# XLAT_AND_JTAG.net
KiCad netlist of a schematic drawn in Altium Designer
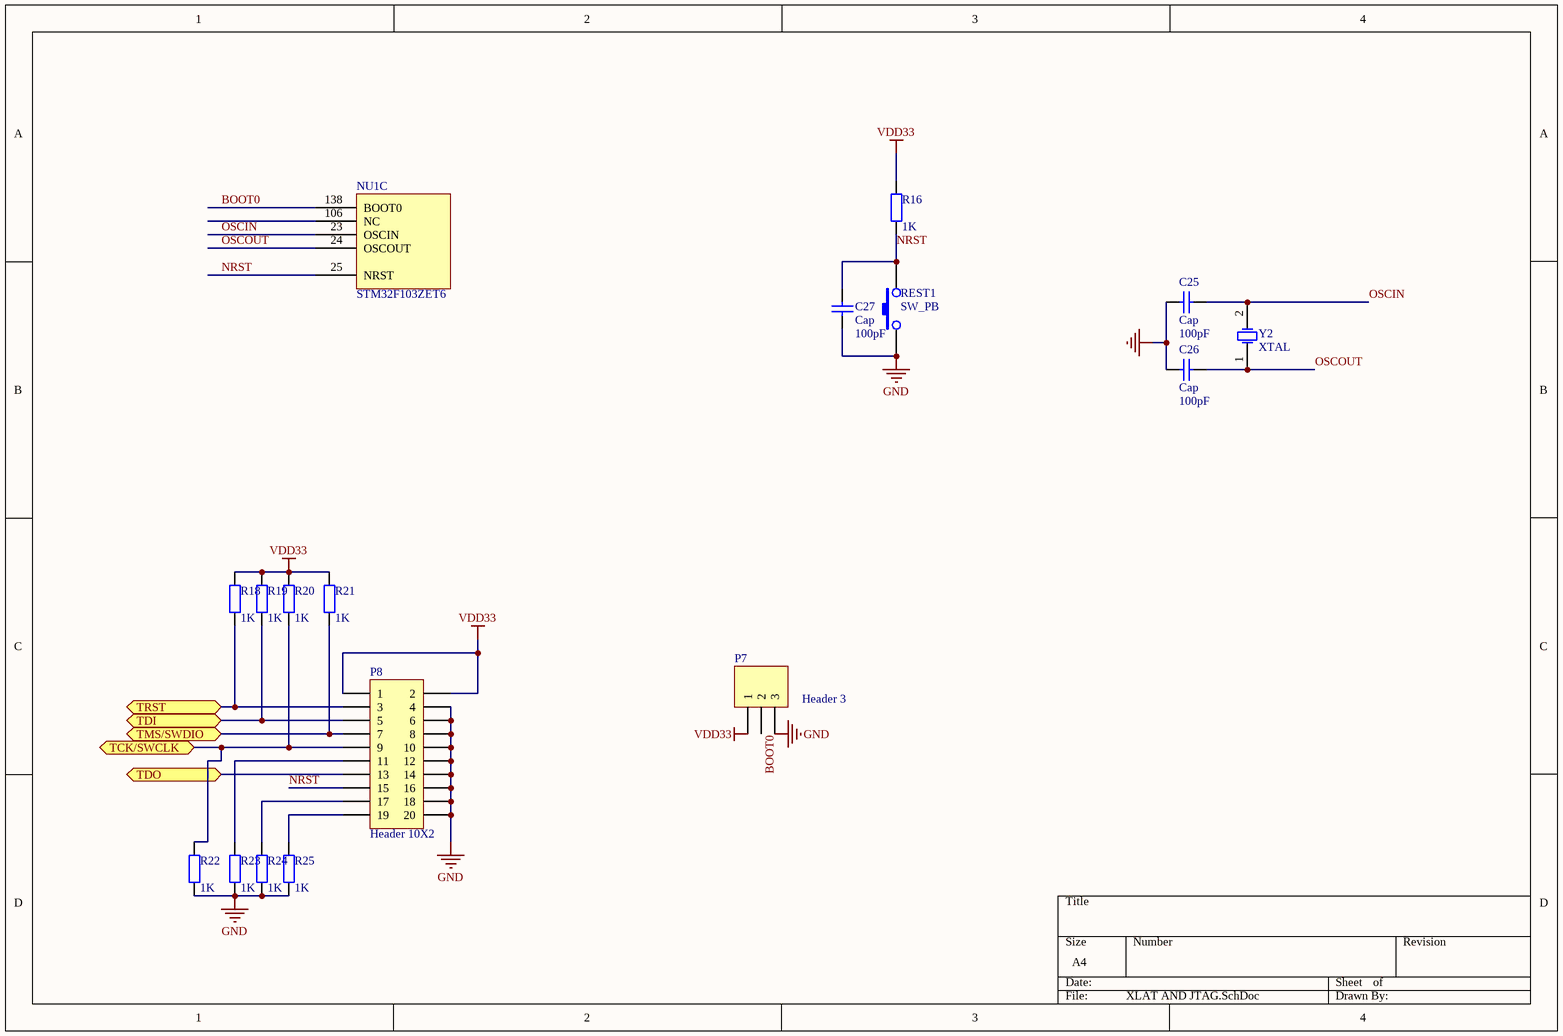
[diagram p0: XLAT AND JTAG.SchDoc]

(export (version "E")
  (design (tool "Eeschema 10.0.6"))
  (components
    (comp (ref "C25")
      (value "Cap")
      (footprint "0805")
      (description "Capacitor")
      (fields (field (name "ALTIUM_VALUE") "100pF") (field (name "PUBLISHER") "Altium Limited"))
      (libsource (lib "Miscellaneous Devices") (part "Cap"))
    )
    (comp (ref "C26")
      (value "Cap")
      (footprint "0805")
      (description "Capacitor")
      (fields (field (name "ALTIUM_VALUE") "100pF") (field (name "PUBLISHER") "Altium Limited"))
      (libsource (lib "Miscellaneous Devices") (part "Cap"))
    )
    (comp (ref "C27")
      (value "Cap")
      (footprint "0805")
      (description "Capacitor")
      (fields (field (name "ALTIUM_VALUE") "100pF") (field (name "PUBLISHER") "Altium Limited"))
      (libsource (lib "Miscellaneous Devices") (part "Cap"))
    )
    (comp (ref "NU1")
      (value "STM32F103ZET6")
      (footprint "LQFN144")
      (libsource (lib "Schlib1") (part "STM32F103ZET6"))
    )
    (comp (ref "P7")
      (value "Header 3")
      (footprint "HDR1X3")
      (description "Header, 3-Pin")
      (fields (field (name "PUBLISHER") "Altium Limited"))
      (libsource (lib "Miscellaneous Connectors") (part "Header 3"))
    )
    (comp (ref "P8")
      (value "Header 10X2")
      (footprint "HDR2X10")
      (description "Header, 10-Pin, Dual row")
      (fields (field (name "PUBLISHER") "Altium Limited"))
      (libsource (lib "Miscellaneous Connectors") (part "Header 10X2"))
    )
    (comp (ref "R16")
      (value "1K")
      (footprint "0805")
      (description "Resistor")
      (fields (field (name "Comment") "Res2") (field (name "PUBLISHER") "Altium Limited"))
      (libsource (lib "Miscellaneous Devices") (part "Res2"))
    )
    (comp (ref "R18")
      (value "1K")
      (footprint "0805")
      (description "Resistor")
      (fields (field (name "Comment") "Res2") (field (name "PUBLISHER") "Altium Limited"))
      (libsource (lib "Miscellaneous Devices") (part "Res2"))
    )
    (comp (ref "R19")
      (value "1K")
      (footprint "0805")
      (description "Resistor")
      (fields (field (name "Comment") "Res2") (field (name "PUBLISHER") "Altium Limited"))
      (libsource (lib "Miscellaneous Devices") (part "Res2"))
    )
    (comp (ref "R20")
      (value "1K")
      (footprint "0805")
      (description "Resistor")
      (fields (field (name "Comment") "Res2") (field (name "PUBLISHER") "Altium Limited"))
      (libsource (lib "Miscellaneous Devices") (part "Res2"))
    )
    (comp (ref "R21")
      (value "1K")
      (footprint "0805")
      (description "Resistor")
      (fields (field (name "Comment") "Res2") (field (name "PUBLISHER") "Altium Limited"))
      (libsource (lib "Miscellaneous Devices") (part "Res2"))
    )
    (comp (ref "R22")
      (value "1K")
      (footprint "0805")
      (description "Resistor")
      (fields (field (name "Comment") "Res2") (field (name "PUBLISHER") "Altium Limited"))
      (libsource (lib "") (part "Res2_1"))
    )
    (comp (ref "R23")
      (value "1K")
      (footprint "0805")
      (description "Resistor")
      (fields (field (name "Comment") "Res2") (field (name "PUBLISHER") "Altium Limited"))
      (libsource (lib "") (part "Res2_1"))
    )
    (comp (ref "R24")
      (value "1K")
      (footprint "0805")
      (description "Resistor")
      (fields (field (name "Comment") "Res2") (field (name "PUBLISHER") "Altium Limited"))
      (libsource (lib "") (part "Res2_1"))
    )
    (comp (ref "R25")
      (value "1K")
      (footprint "0805")
      (description "Resistor")
      (fields (field (name "Comment") "Res2") (field (name "PUBLISHER") "Altium Limited"))
      (libsource (lib "") (part "Res2_1"))
    )
    (comp (ref "REST1") (value "SW_PB") (footprint "SWPB") (libsource (lib "*") (part "SW_PB")))
    (comp (ref "Y2")
      (value "XTAL")
      (footprint "XTAL-1")
      (description "Crystal Oscillator")
      (fields (field (name "PUBLISHER") "Altium Limited"))
      (libsource (lib "Miscellaneous Devices") (part "XTAL"))
    )
  )
  (nets
    (net (code "1") (name "/BOOT0") (class "Default")
      (node (ref "NU1") (pin "138") (pinfunction "BOOT0_138") (pintype "passive"))
      (node (ref "P7") (pin "2") (pinfunction "2_2") (pintype "passive"))
    )
    (net (code "2") (name "/NRST") (class "Default")
      (node (ref "C27") (pin "2") (pinfunction "2_2") (pintype "passive"))
      (node (ref "NU1") (pin "25") (pinfunction "NRST_25") (pintype "passive"))
      (node (ref "P8") (pin "15") (pinfunction "15_15") (pintype "passive"))
      (node (ref "R16") (pin "1") (pinfunction "1_1") (pintype "passive"))
      (node (ref "REST1") (pin "2") (pinfunction "2_2") (pintype "passive"))
    )
    (net (code "3") (name "/OSCIN") (class "Default")
      (node (ref "C25") (pin "2") (pinfunction "2_2") (pintype "passive"))
      (node (ref "NU1") (pin "23") (pinfunction "OSCIN_23") (pintype "passive"))
      (node (ref "Y2") (pin "2") (pinfunction "OSC2_2") (pintype "passive"))
    )
    (net (code "4") (name "/OSCOUT") (class "Default")
      (node (ref "C26") (pin "2") (pinfunction "2_2") (pintype "passive"))
      (node (ref "NU1") (pin "24") (pinfunction "OSCOUT_24") (pintype "passive"))
      (node (ref "Y2") (pin "1") (pinfunction "OSC1_1") (pintype "passive"))
    )
    (net (code "5") (name "/TCK{slash}SWCLK") (class "Default")
      (node (ref "P8") (pin "9") (pinfunction "9_9") (pintype "passive"))
      (node (ref "R20") (pin "1") (pinfunction "1_1") (pintype "passive"))
      (node (ref "R22") (pin "1") (pinfunction "1_1") (pintype "passive"))
    )
    (net (code "6") (name "/TDI") (class "Default")
      (node (ref "P8") (pin "5") (pinfunction "5_5") (pintype "passive"))
      (node (ref "R19") (pin "1") (pinfunction "1_1") (pintype "passive"))
    )
    (net (code "7") (name "/TDO") (class "Default")
      (node (ref "P8") (pin "13") (pinfunction "13_13") (pintype "passive"))
    )
    (net (code "8") (name "/TMS{slash}SWDIO") (class "Default")
      (node (ref "P8") (pin "7") (pinfunction "7_7") (pintype "passive"))
      (node (ref "R21") (pin "1") (pinfunction "1_1") (pintype "passive"))
    )
    (net (code "9") (name "/TRST") (class "Default")
      (node (ref "P8") (pin "3") (pinfunction "3_3") (pintype "passive"))
      (node (ref "R18") (pin "1") (pinfunction "1_1") (pintype "passive"))
    )
    (net (code "10") (name "GND") (class "Default")
      (node (ref "C25") (pin "1") (pinfunction "1_1") (pintype "passive"))
      (node (ref "C26") (pin "1") (pinfunction "1_1") (pintype "passive"))
      (node (ref "C27") (pin "1") (pinfunction "1_1") (pintype "passive"))
      (node (ref "P7") (pin "3") (pinfunction "3_3") (pintype "passive"))
      (node (ref "P8") (pin "10") (pinfunction "10_10") (pintype "passive"))
      (node (ref "P8") (pin "12") (pinfunction "12_12") (pintype "passive"))
      (node (ref "P8") (pin "14") (pinfunction "14_14") (pintype "passive"))
      (node (ref "P8") (pin "16") (pinfunction "16_16") (pintype "passive"))
      (node (ref "P8") (pin "18") (pinfunction "18_18") (pintype "passive"))
      (node (ref "P8") (pin "20") (pinfunction "20_20") (pintype "passive"))
      (node (ref "P8") (pin "4") (pinfunction "4_4") (pintype "passive"))
      (node (ref "P8") (pin "6") (pinfunction "6_6") (pintype "passive"))
      (node (ref "P8") (pin "8") (pinfunction "8_8") (pintype "passive"))
      (node (ref "R22") (pin "2") (pinfunction "2_2") (pintype "passive"))
      (node (ref "R23") (pin "2") (pinfunction "2_2") (pintype "passive"))
      (node (ref "R24") (pin "2") (pinfunction "2_2") (pintype "passive"))
      (node (ref "R25") (pin "2") (pinfunction "2_2") (pintype "passive"))
      (node (ref "REST1") (pin "1") (pinfunction "1_1") (pintype "passive"))
    )
    (net (code "11") (name "Net-(P8-Pad11)") (class "Default")
      (node (ref "P8") (pin "11") (pinfunction "11_11") (pintype "passive"))
      (node (ref "R23") (pin "1") (pinfunction "1_1") (pintype "passive"))
    )
    (net (code "12") (name "Net-(P8-Pad17)") (class "Default")
      (node (ref "P8") (pin "17") (pinfunction "17_17") (pintype "passive"))
      (node (ref "R24") (pin "1") (pinfunction "1_1") (pintype "passive"))
    )
    (net (code "13") (name "Net-(P8-Pad19)") (class "Default")
      (node (ref "P8") (pin "19") (pinfunction "19_19") (pintype "passive"))
      (node (ref "R25") (pin "1") (pinfunction "1_1") (pintype "passive"))
    )
    (net (code "14") (name "VDD33") (class "Default")
      (node (ref "P7") (pin "1") (pinfunction "1_1") (pintype "passive"))
      (node (ref "P8") (pin "1") (pinfunction "1_1") (pintype "passive"))
      (node (ref "P8") (pin "2") (pinfunction "2_2") (pintype "passive"))
      (node (ref "R16") (pin "2") (pinfunction "2_2") (pintype "passive"))
      (node (ref "R18") (pin "2") (pinfunction "2_2") (pintype "passive"))
      (node (ref "R19") (pin "2") (pinfunction "2_2") (pintype "passive"))
      (node (ref "R20") (pin "2") (pinfunction "2_2") (pintype "passive"))
      (node (ref "R21") (pin "2") (pinfunction "2_2") (pintype "passive"))
    )
    (net (code "15") (name "unconnected-(NU1C-NC-Pad106)") (class "Default")
      (node (ref "NU1") (pin "106") (pinfunction "NC_106") (pintype "passive"))
    )
  )
)
